# I2C_Multiplexers.net
KiCad netlist of a schematic drawn in Altium Designer
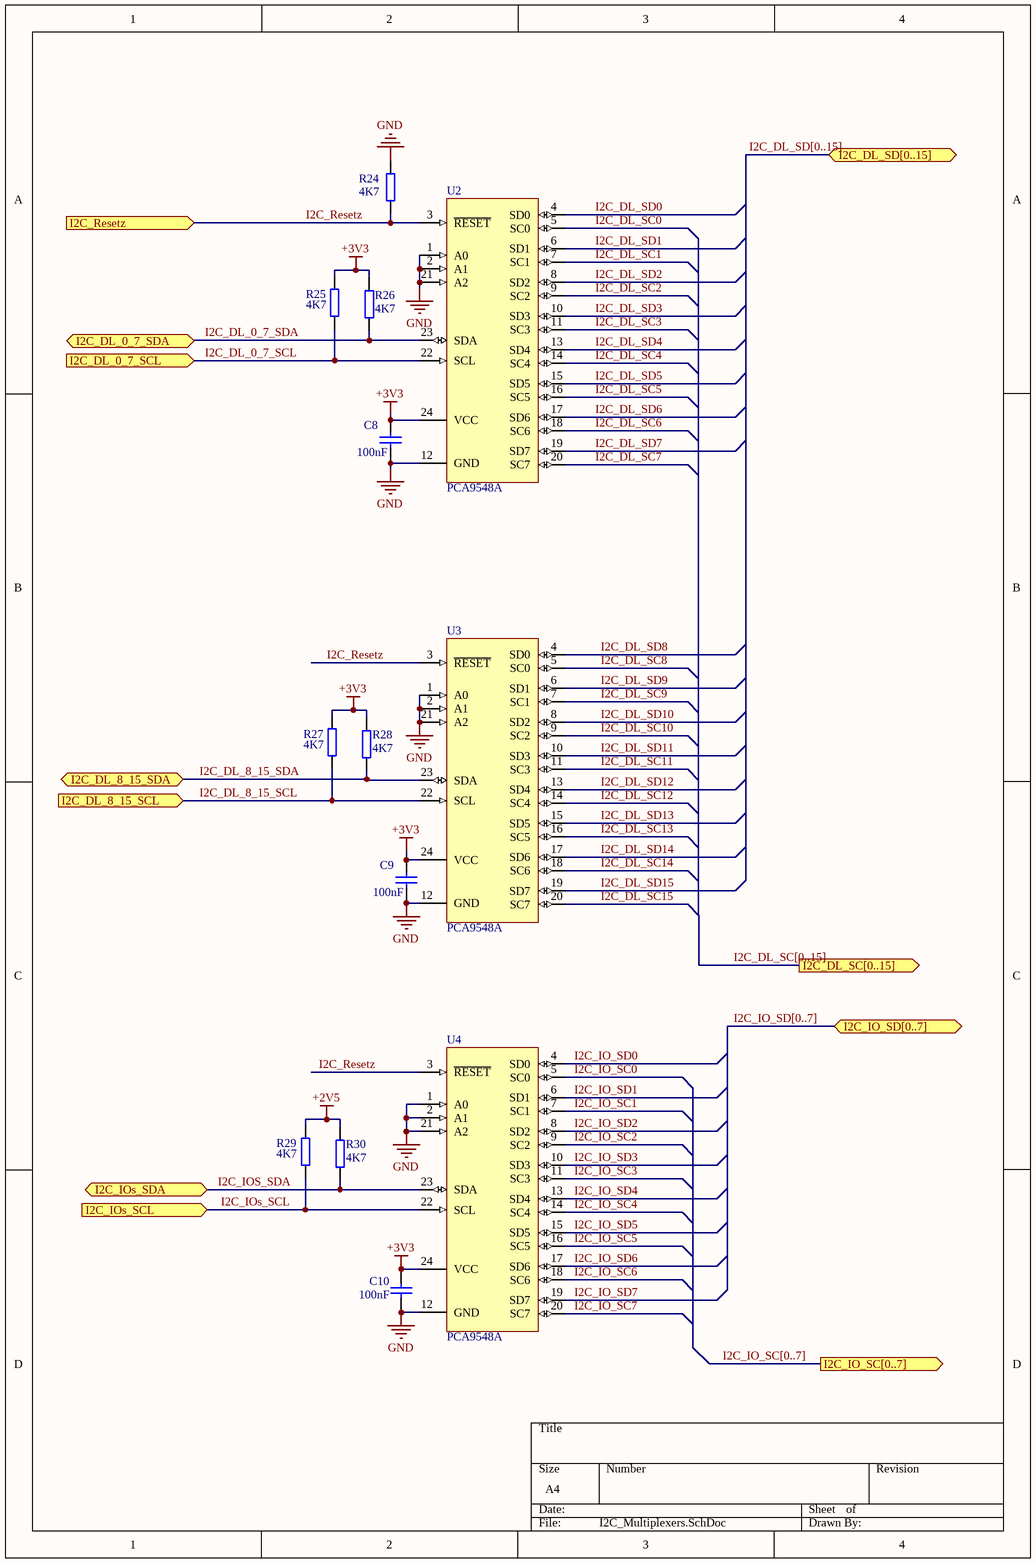
[diagram p0: I2C_Multiplexers.SchDoc]

(export (version "E")
  (design (tool "Eeschema 10.0.6"))
  (components
    (comp (ref "C8")
      (value "100nF")
      (footprint "CC1608-0603")
      (description "Capacitor")
      (fields
        (field (name "TOLERANCE") "±10%")
        (field (name "VOLTAGE") "16V")
        (field (name "PUBLISHER") "Altium Limited")
      )
      (libsource (lib "wr_switch") (part "Cap"))
    )
    (comp (ref "C9")
      (value "100nF")
      (footprint "CC1608-0603")
      (description "Capacitor")
      (fields
        (field (name "TOLERANCE") "±10%")
        (field (name "VOLTAGE") "16V")
        (field (name "PUBLISHER") "Altium Limited")
      )
      (libsource (lib "wr_switch") (part "Cap"))
    )
    (comp (ref "C10")
      (value "100nF")
      (footprint "CC1608-0603")
      (description "Capacitor")
      (fields
        (field (name "TOLERANCE") "±10%")
        (field (name "VOLTAGE") "16V")
        (field (name "PUBLISHER") "Altium Limited")
      )
      (libsource (lib "wr_switch") (part "Cap"))
    )
    (comp (ref "R24")
      (value "4K7")
      (footprint "0603")
      (description "SMD Resistor")
      (fields (field (name "TOLERANCE") "±1%"))
      (libsource (lib "wr_switch") (part "RES_SMD"))
    )
    (comp (ref "R25")
      (value "4K7")
      (footprint "0603")
      (description "SMD Resistor")
      (fields (field (name "TOLERANCE") "±1%"))
      (libsource (lib "wr_switch") (part "RES_SMD"))
    )
    (comp (ref "R26")
      (value "4K7")
      (footprint "0603")
      (description "SMD Resistor")
      (fields (field (name "TOLERANCE") "±1%"))
      (libsource (lib "wr_switch") (part "RES_SMD"))
    )
    (comp (ref "R27")
      (value "4K7")
      (footprint "0603")
      (description "SMD Resistor")
      (fields (field (name "TOLERANCE") "±1%"))
      (libsource (lib "wr_switch") (part "RES_SMD"))
    )
    (comp (ref "R28")
      (value "4K7")
      (footprint "0603")
      (description "SMD Resistor")
      (fields (field (name "TOLERANCE") "±1%"))
      (libsource (lib "wr_switch") (part "RES_SMD"))
    )
    (comp (ref "R29")
      (value "4K7")
      (footprint "0603")
      (description "SMD Resistor")
      (fields (field (name "TOLERANCE") "±1%"))
      (libsource (lib "wr_switch") (part "RES_SMD"))
    )
    (comp (ref "R30")
      (value "4K7")
      (footprint "0603")
      (description "SMD Resistor")
      (fields (field (name "TOLERANCE") "±1%"))
      (libsource (lib "wr_switch") (part "RES_SMD"))
    )
    (comp (ref "U2")
      (value "PCA9548A")
      (footprint "SOP65P640X120-24N")
      (description "8-channel 2C-bus switch with reset")
      (libsource (lib "wr_switch") (part "PCA9548A"))
    )
    (comp (ref "U3")
      (value "PCA9548A")
      (footprint "SOP65P640X120-24N")
      (description "8-channel 2C-bus switch with reset")
      (libsource (lib "wr_switch") (part "PCA9548A"))
    )
    (comp (ref "U4")
      (value "PCA9548A")
      (footprint "SOP65P640X120-24N")
      (description "8-channel 2C-bus switch with reset")
      (libsource (lib "wr_switch") (part "PCA9548A"))
    )
  )
  (nets
    (net (code "1") (name "+2V5") (class "Default")
      (node (ref "R29") (pin "1") (pinfunction "1_1") (pintype "passive"))
      (node (ref "R30") (pin "1") (pinfunction "1_1") (pintype "passive"))
    )
    (net (code "2") (name "+3V3") (class "Default")
      (node (ref "C10") (pin "1") (pinfunction "1_1") (pintype "passive"))
      (node (ref "C8") (pin "2") (pinfunction "2_2") (pintype "passive"))
      (node (ref "C9") (pin "2") (pinfunction "2_2") (pintype "passive"))
      (node (ref "R25") (pin "1") (pinfunction "1_1") (pintype "passive"))
      (node (ref "R26") (pin "1") (pinfunction "1_1") (pintype "passive"))
      (node (ref "R27") (pin "1") (pinfunction "1_1") (pintype "passive"))
      (node (ref "R28") (pin "1") (pinfunction "1_1") (pintype "passive"))
      (node (ref "U2") (pin "24") (pinfunction "VCC_24") (pintype "power_in"))
      (node (ref "U3") (pin "24") (pinfunction "VCC_24") (pintype "power_in"))
      (node (ref "U4") (pin "24") (pinfunction "VCC_24") (pintype "power_in"))
    )
    (net (code "3") (name "/I2C_DL_0_7_SCL") (class "Default")
      (node (ref "R25") (pin "2") (pinfunction "2_2") (pintype "passive"))
      (node (ref "U2") (pin "22") (pinfunction "SCL_22") (pintype "input"))
    )
    (net (code "4") (name "/I2C_DL_0_7_SDA") (class "Default")
      (node (ref "R26") (pin "2") (pinfunction "2_2") (pintype "passive"))
      (node (ref "U2") (pin "23") (pinfunction "SDA_23") (pintype "bidirectional"))
    )
    (net (code "5") (name "/I2C_DL_8_15_SCL") (class "Default")
      (node (ref "R27") (pin "2") (pinfunction "2_2") (pintype "passive"))
      (node (ref "U3") (pin "22") (pinfunction "SCL_22") (pintype "input"))
    )
    (net (code "6") (name "/I2C_DL_8_15_SDA") (class "Default")
      (node (ref "R28") (pin "2") (pinfunction "2_2") (pintype "passive"))
      (node (ref "U3") (pin "23") (pinfunction "SDA_23") (pintype "bidirectional"))
    )
    (net (code "7") (name "/I2C_DL_SC0") (class "Default")
      (node (ref "U2") (pin "5") (pinfunction "SC0_5") (pintype "bidirectional"))
    )
    (net (code "8") (name "/I2C_DL_SC1") (class "Default")
      (node (ref "U2") (pin "7") (pinfunction "SC1_7") (pintype "bidirectional"))
    )
    (net (code "9") (name "/I2C_DL_SC2") (class "Default")
      (node (ref "U2") (pin "9") (pinfunction "SC2_9") (pintype "bidirectional"))
    )
    (net (code "10") (name "/I2C_DL_SC3") (class "Default")
      (node (ref "U2") (pin "11") (pinfunction "SC3_11") (pintype "bidirectional"))
    )
    (net (code "11") (name "/I2C_DL_SC4") (class "Default")
      (node (ref "U2") (pin "14") (pinfunction "SC4_14") (pintype "bidirectional"))
    )
    (net (code "12") (name "/I2C_DL_SC5") (class "Default")
      (node (ref "U2") (pin "16") (pinfunction "SC5_16") (pintype "bidirectional"))
    )
    (net (code "13") (name "/I2C_DL_SC6") (class "Default")
      (node (ref "U2") (pin "18") (pinfunction "SC6_18") (pintype "bidirectional"))
    )
    (net (code "14") (name "/I2C_DL_SC7") (class "Default")
      (node (ref "U2") (pin "20") (pinfunction "SC7_20") (pintype "bidirectional"))
    )
    (net (code "15") (name "/I2C_DL_SC8") (class "Default")
      (node (ref "U3") (pin "5") (pinfunction "SC0_5") (pintype "bidirectional"))
    )
    (net (code "16") (name "/I2C_DL_SC9") (class "Default")
      (node (ref "U3") (pin "7") (pinfunction "SC1_7") (pintype "bidirectional"))
    )
    (net (code "17") (name "/I2C_DL_SC10") (class "Default")
      (node (ref "U3") (pin "9") (pinfunction "SC2_9") (pintype "bidirectional"))
    )
    (net (code "18") (name "/I2C_DL_SC11") (class "Default")
      (node (ref "U3") (pin "11") (pinfunction "SC3_11") (pintype "bidirectional"))
    )
    (net (code "19") (name "/I2C_DL_SC12") (class "Default")
      (node (ref "U3") (pin "14") (pinfunction "SC4_14") (pintype "bidirectional"))
    )
    (net (code "20") (name "/I2C_DL_SC13") (class "Default")
      (node (ref "U3") (pin "16") (pinfunction "SC5_16") (pintype "bidirectional"))
    )
    (net (code "21") (name "/I2C_DL_SC14") (class "Default")
      (node (ref "U3") (pin "18") (pinfunction "SC6_18") (pintype "bidirectional"))
    )
    (net (code "22") (name "/I2C_DL_SC15") (class "Default")
      (node (ref "U3") (pin "20") (pinfunction "SC7_20") (pintype "bidirectional"))
    )
    (net (code "24") (name "/I2C_DL_SD0") (class "Default")
      (node (ref "U2") (pin "4") (pinfunction "SD0_4") (pintype "bidirectional"))
    )
    (net (code "25") (name "/I2C_DL_SD1") (class "Default")
      (node (ref "U2") (pin "6") (pinfunction "SD1_6") (pintype "bidirectional"))
    )
    (net (code "26") (name "/I2C_DL_SD2") (class "Default")
      (node (ref "U2") (pin "8") (pinfunction "SD2_8") (pintype "bidirectional"))
    )
    (net (code "27") (name "/I2C_DL_SD3") (class "Default")
      (node (ref "U2") (pin "10") (pinfunction "SD3_10") (pintype "bidirectional"))
    )
    (net (code "28") (name "/I2C_DL_SD4") (class "Default")
      (node (ref "U2") (pin "13") (pinfunction "SD4_13") (pintype "bidirectional"))
    )
    (net (code "29") (name "/I2C_DL_SD5") (class "Default")
      (node (ref "U2") (pin "15") (pinfunction "SD5_15") (pintype "bidirectional"))
    )
    (net (code "30") (name "/I2C_DL_SD6") (class "Default")
      (node (ref "U2") (pin "17") (pinfunction "SD6_17") (pintype "bidirectional"))
    )
    (net (code "31") (name "/I2C_DL_SD7") (class "Default")
      (node (ref "U2") (pin "19") (pinfunction "SD7_19") (pintype "bidirectional"))
    )
    (net (code "32") (name "/I2C_DL_SD8") (class "Default")
      (node (ref "U3") (pin "4") (pinfunction "SD0_4") (pintype "bidirectional"))
    )
    (net (code "33") (name "/I2C_DL_SD9") (class "Default")
      (node (ref "U3") (pin "6") (pinfunction "SD1_6") (pintype "bidirectional"))
    )
    (net (code "34") (name "/I2C_DL_SD10") (class "Default")
      (node (ref "U3") (pin "8") (pinfunction "SD2_8") (pintype "bidirectional"))
    )
    (net (code "35") (name "/I2C_DL_SD11") (class "Default")
      (node (ref "U3") (pin "10") (pinfunction "SD3_10") (pintype "bidirectional"))
    )
    (net (code "36") (name "/I2C_DL_SD12") (class "Default")
      (node (ref "U3") (pin "13") (pinfunction "SD4_13") (pintype "bidirectional"))
    )
    (net (code "37") (name "/I2C_DL_SD13") (class "Default")
      (node (ref "U3") (pin "15") (pinfunction "SD5_15") (pintype "bidirectional"))
    )
    (net (code "38") (name "/I2C_DL_SD14") (class "Default")
      (node (ref "U3") (pin "17") (pinfunction "SD6_17") (pintype "bidirectional"))
    )
    (net (code "39") (name "/I2C_DL_SD15") (class "Default")
      (node (ref "U3") (pin "19") (pinfunction "SD7_19") (pintype "bidirectional"))
    )
    (net (code "41") (name "/I2C_IOS_SDA") (class "Default")
      (node (ref "R30") (pin "2") (pinfunction "2_2") (pintype "passive"))
      (node (ref "U4") (pin "23") (pinfunction "SDA_23") (pintype "bidirectional"))
    )
    (net (code "42") (name "/I2C_IO_SC0") (class "Default")
      (node (ref "U4") (pin "5") (pinfunction "SC0_5") (pintype "bidirectional"))
    )
    (net (code "43") (name "/I2C_IO_SC1") (class "Default")
      (node (ref "U4") (pin "7") (pinfunction "SC1_7") (pintype "bidirectional"))
    )
    (net (code "44") (name "/I2C_IO_SC2") (class "Default")
      (node (ref "U4") (pin "9") (pinfunction "SC2_9") (pintype "bidirectional"))
    )
    (net (code "45") (name "/I2C_IO_SC3") (class "Default")
      (node (ref "U4") (pin "11") (pinfunction "SC3_11") (pintype "bidirectional"))
    )
    (net (code "46") (name "/I2C_IO_SC4") (class "Default")
      (node (ref "U4") (pin "14") (pinfunction "SC4_14") (pintype "bidirectional"))
    )
    (net (code "47") (name "/I2C_IO_SC5") (class "Default")
      (node (ref "U4") (pin "16") (pinfunction "SC5_16") (pintype "bidirectional"))
    )
    (net (code "48") (name "/I2C_IO_SC6") (class "Default")
      (node (ref "U4") (pin "18") (pinfunction "SC6_18") (pintype "bidirectional"))
    )
    (net (code "49") (name "/I2C_IO_SC7") (class "Default")
      (node (ref "U4") (pin "20") (pinfunction "SC7_20") (pintype "bidirectional"))
    )
    (net (code "51") (name "/I2C_IO_SD0") (class "Default")
      (node (ref "U4") (pin "4") (pinfunction "SD0_4") (pintype "bidirectional"))
    )
    (net (code "52") (name "/I2C_IO_SD1") (class "Default")
      (node (ref "U4") (pin "6") (pinfunction "SD1_6") (pintype "bidirectional"))
    )
    (net (code "53") (name "/I2C_IO_SD2") (class "Default")
      (node (ref "U4") (pin "8") (pinfunction "SD2_8") (pintype "bidirectional"))
    )
    (net (code "54") (name "/I2C_IO_SD3") (class "Default")
      (node (ref "U4") (pin "10") (pinfunction "SD3_10") (pintype "bidirectional"))
    )
    (net (code "55") (name "/I2C_IO_SD4") (class "Default")
      (node (ref "U4") (pin "13") (pinfunction "SD4_13") (pintype "bidirectional"))
    )
    (net (code "56") (name "/I2C_IO_SD5") (class "Default")
      (node (ref "U4") (pin "15") (pinfunction "SD5_15") (pintype "bidirectional"))
    )
    (net (code "57") (name "/I2C_IO_SD6") (class "Default")
      (node (ref "U4") (pin "17") (pinfunction "SD6_17") (pintype "bidirectional"))
    )
    (net (code "58") (name "/I2C_IO_SD7") (class "Default")
      (node (ref "U4") (pin "19") (pinfunction "SD7_19") (pintype "bidirectional"))
    )
    (net (code "60") (name "/I2C_IOs_SCL") (class "Default")
      (node (ref "R29") (pin "2") (pinfunction "2_2") (pintype "passive"))
      (node (ref "U4") (pin "22") (pinfunction "SCL_22") (pintype "input"))
    )
    (net (code "61") (name "/I2C_Resetz") (class "Default")
      (node (ref "R24") (pin "1") (pinfunction "1_1") (pintype "passive"))
      (node (ref "U2") (pin "3") (pinfunction "~{RESET}_3") (pintype "input"))
      (node (ref "U3") (pin "3") (pinfunction "~{RESET}_3") (pintype "input"))
      (node (ref "U4") (pin "3") (pinfunction "~{RESET}_3") (pintype "input"))
    )
    (net (code "62") (name "GND") (class "Default")
      (node (ref "C10") (pin "2") (pinfunction "2_2") (pintype "passive"))
      (node (ref "C8") (pin "1") (pinfunction "1_1") (pintype "passive"))
      (node (ref "C9") (pin "1") (pinfunction "1_1") (pintype "passive"))
      (node (ref "R24") (pin "2") (pinfunction "2_2") (pintype "passive"))
      (node (ref "U2") (pin "1") (pinfunction "A0_1") (pintype "input"))
      (node (ref "U2") (pin "12") (pinfunction "GND_12") (pintype "power_in"))
      (node (ref "U2") (pin "2") (pinfunction "A1_2") (pintype "input"))
      (node (ref "U2") (pin "21") (pinfunction "A2_21") (pintype "input"))
      (node (ref "U3") (pin "1") (pinfunction "A0_1") (pintype "input"))
      (node (ref "U3") (pin "12") (pinfunction "GND_12") (pintype "power_in"))
      (node (ref "U3") (pin "2") (pinfunction "A1_2") (pintype "input"))
      (node (ref "U3") (pin "21") (pinfunction "A2_21") (pintype "input"))
      (node (ref "U4") (pin "1") (pinfunction "A0_1") (pintype "input"))
      (node (ref "U4") (pin "12") (pinfunction "GND_12") (pintype "power_in"))
      (node (ref "U4") (pin "2") (pinfunction "A1_2") (pintype "input"))
      (node (ref "U4") (pin "21") (pinfunction "A2_21") (pintype "input"))
    )
  )
)
